# ToF.net
KiCad netlist of a schematic drawn in Altium Designer
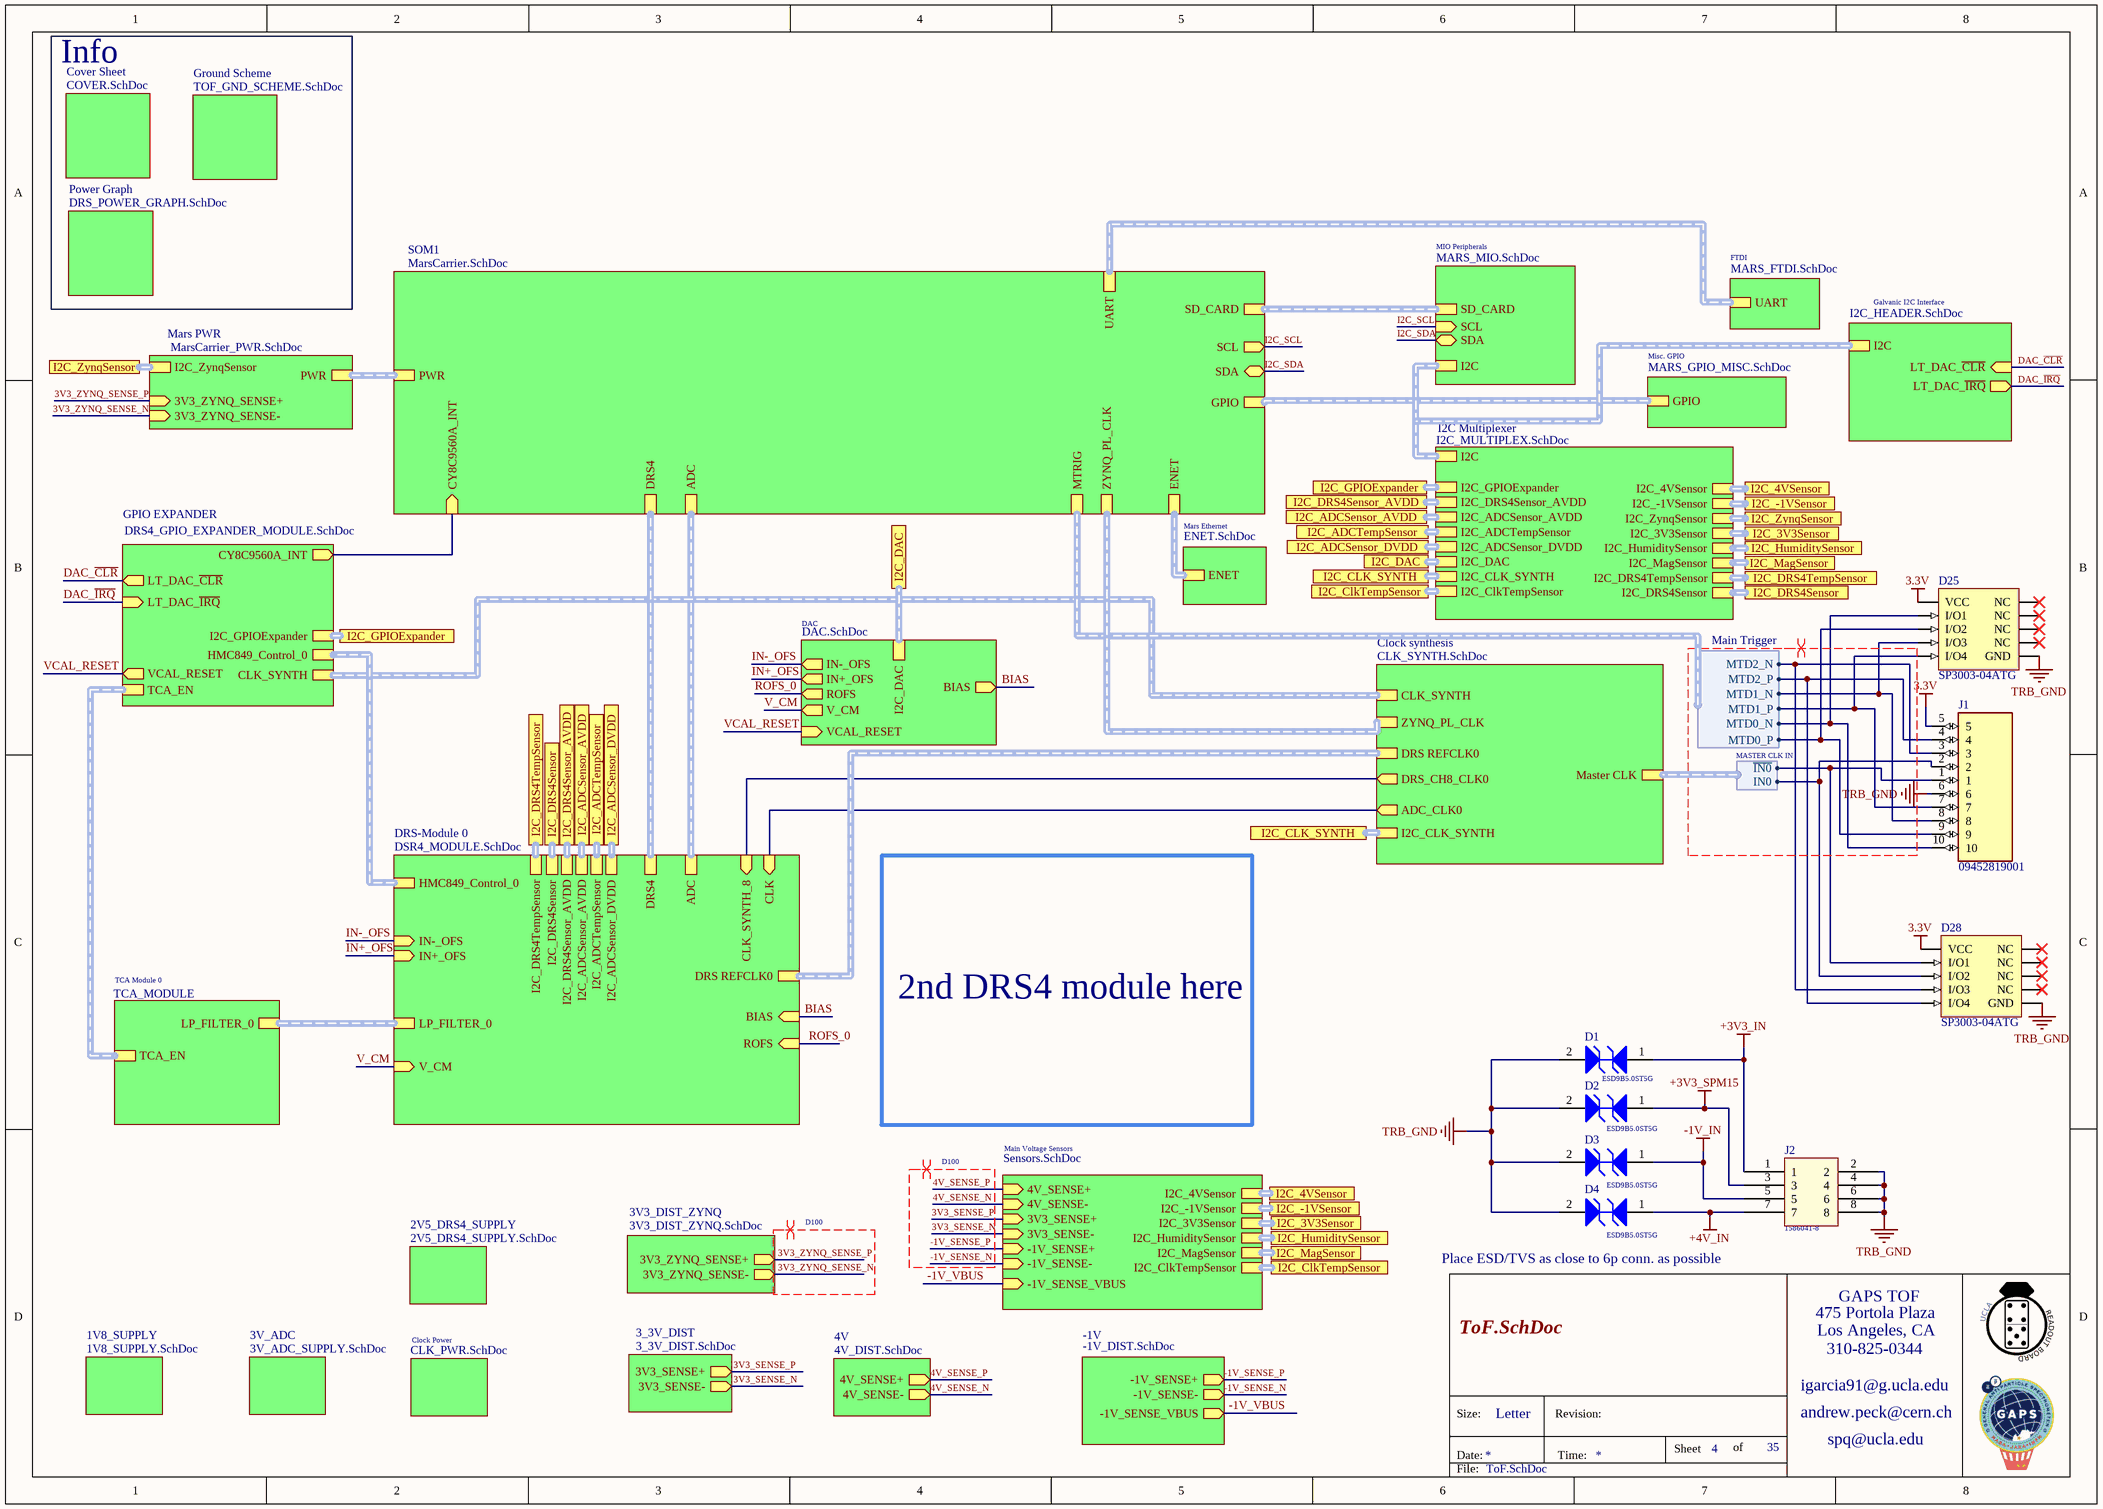
[diagram p0: ToF.SchDoc]

(export (version "E")
  (design (tool "Eeschema 10.0.6"))
  (components
    (comp (ref "D1")
      (value "ESD9B5.0ST5G")
      (footprint "ONSC-SOD-923-2-514AB-01_V")
      (fields (field (name "MANUFACTURER") "On Semiconductor"))
      (libsource (lib "On_Semiconductor_ESD9B5_0ST5G") (part "ESD9B5.0ST5G"))
    )
    (comp (ref "D2")
      (value "ESD9B5.0ST5G")
      (footprint "ONSC-SOD-923-2-514AB-01_V")
      (fields (field (name "MANUFACTURER") "On Semiconductor"))
      (libsource (lib "On_Semiconductor_ESD9B5_0ST5G") (part "ESD9B5.0ST5G"))
    )
    (comp (ref "D3")
      (value "ESD9B5.0ST5G")
      (footprint "ONSC-SOD-923-2-514AB-01_V")
      (fields (field (name "MANUFACTURER") "On Semiconductor"))
      (libsource (lib "On_Semiconductor_ESD9B5_0ST5G") (part "ESD9B5.0ST5G"))
    )
    (comp (ref "D4")
      (value "ESD9B5.0ST5G")
      (footprint "ONSC-SOD-923-2-514AB-01_V")
      (fields (field (name "MANUFACTURER") "On Semiconductor"))
      (libsource (lib "On_Semiconductor_ESD9B5_0ST5G") (part "ESD9B5.0ST5G"))
    )
    (comp (ref "D25")
      (value "Diode_SP3003-04ATG_LVDS_ESD")
      (footprint "Diode_SP3003-04ATG_LVDS_ESD")
      (description "ESD Suppressors / TVS Diodes 4 Ch 8kV 0.65pF SPA")
      (fields (field (name "SERIES") "SP3003-04ATG"))
      (libsource (lib "Diode_SP3003-04ATG_LVDS_ESD") (part "Diode_SP3003-04ATG_LVDS_ESD"))
    )
    (comp (ref "D28")
      (value "Diode_SP3003-04ATG_LVDS_ESD")
      (footprint "Diode_SP3003-04ATG_LVDS_ESD")
      (description "ESD Suppressors / TVS Diodes 4 Ch 8kV 0.65pF SPA")
      (fields (field (name "SERIES") "SP3003-04ATG"))
      (libsource (lib "Diode_SP3003-04ATG_LVDS_ESD") (part "Diode_SP3003-04ATG_LVDS_ESD"))
    )
    (comp (ref "J1")
      (value "09452819001")
      (footprint "09452812561")
      (description "Connector")
      (fields (field (name "MOUSER PART NUMBER") "617-09452819001"))
      (libsource (lib "Conn_Harting_09452819001") (part "09452819001"))
    )
    (comp (ref "J2")
      (value "Header_TE_Connectivity_1586041-8_8POS")
      (footprint "Header_TE_Connectivity_1586041-8_8POS")
      (description "Headers & Wire Housings RA HDR W/O PEGS 8P")
      (fields (field (name "SERIES") "1586041-8"))
      (libsource (lib "Header_TE_Connectivity_1586041-8_8POS") (part "Header_TE_Connectivity_1586041-8_8POS"))
    )
  )
  (nets
    (net (code "70") (name "+3V3_IN") (class "Default")
      (node (ref "D1") (pin "1") (pinfunction "A1_1") (pintype "passive"))
      (node (ref "J2") (pin "1") (pinfunction "1_1") (pintype "power_in"))
    )
    (net (code "71") (name "+3V3_SPM15") (class "Default")
      (node (ref "D2") (pin "1") (pinfunction "A1_1") (pintype "passive"))
      (node (ref "J2") (pin "3") (pinfunction "3_3") (pintype "power_in"))
    )
    (net (code "72") (name "+4V_IN") (class "Default")
      (node (ref "D4") (pin "1") (pinfunction "A1_1") (pintype "passive"))
      (node (ref "J2") (pin "7") (pinfunction "7_7") (pintype "power_in"))
    )
    (net (code "73") (name "-1V_IN") (class "Default")
      (node (ref "D3") (pin "1") (pinfunction "A1_1") (pintype "passive"))
      (node (ref "J2") (pin "5") (pinfunction "5_5") (pintype "power_in"))
    )
    (net (code "128") (name "3.3V") (class "Default")
      (node (ref "D25") (pin "3") (pinfunction "VCC_3") (pintype "passive"))
      (node (ref "D28") (pin "3") (pinfunction "VCC_3") (pintype "passive"))
      (node (ref "J1") (pin "5") (pinfunction "5_5") (pintype "bidirectional"))
    )
    (net (code "129") (name "Net-(D25-I{slash}O1)") (class "Default")
      (node (ref "D25") (pin "1") (pinfunction "I/O1_1") (pintype "input"))
      (node (ref "J1") (pin "10") (pinfunction "10_10") (pintype "bidirectional"))
    )
    (net (code "130") (name "Net-(D25-I{slash}O2)") (class "Default")
      (node (ref "D25") (pin "2") (pinfunction "I/O2_2") (pintype "input"))
      (node (ref "J1") (pin "9") (pinfunction "9_9") (pintype "bidirectional"))
    )
    (net (code "131") (name "Net-(D25-I{slash}O3)") (class "Default")
      (node (ref "D25") (pin "4") (pinfunction "I/O3_4") (pintype "input"))
      (node (ref "J1") (pin "8") (pinfunction "8_8") (pintype "bidirectional"))
    )
    (net (code "132") (name "Net-(D25-I{slash}O4)") (class "Default")
      (node (ref "D25") (pin "5") (pinfunction "I/O4_5") (pintype "input"))
      (node (ref "J1") (pin "7") (pinfunction "7_7") (pintype "bidirectional"))
    )
    (net (code "133") (name "Net-(D28-I{slash}O1)") (class "Default")
      (node (ref "D28") (pin "1") (pinfunction "I/O1_1") (pintype "input"))
      (node (ref "J1") (pin "1") (pinfunction "1_1") (pintype "bidirectional"))
    )
    (net (code "134") (name "Net-(D28-I{slash}O2)") (class "Default")
      (node (ref "D28") (pin "2") (pinfunction "I/O2_2") (pintype "input"))
      (node (ref "J1") (pin "2") (pinfunction "2_2") (pintype "bidirectional"))
    )
    (net (code "135") (name "Net-(D28-I{slash}O3)") (class "Default")
      (node (ref "D28") (pin "4") (pinfunction "I/O3_4") (pintype "input"))
      (node (ref "J1") (pin "3") (pinfunction "3_3") (pintype "bidirectional"))
    )
    (net (code "136") (name "Net-(D28-I{slash}O4)") (class "Default")
      (node (ref "D28") (pin "5") (pinfunction "I/O4_5") (pintype "input"))
      (node (ref "J1") (pin "4") (pinfunction "4_4") (pintype "bidirectional"))
    )
    (net (code "137") (name "TRB_GND") (class "Default")
      (node (ref "D1") (pin "2") (pinfunction "A2_2") (pintype "passive"))
      (node (ref "D2") (pin "2") (pinfunction "A2_2") (pintype "passive"))
      (node (ref "D25") (pin "8") (pinfunction "GND_8") (pintype "power_in"))
      (node (ref "D28") (pin "8") (pinfunction "GND_8") (pintype "power_in"))
      (node (ref "D3") (pin "2") (pinfunction "A2_2") (pintype "passive"))
      (node (ref "D4") (pin "2") (pinfunction "A2_2") (pintype "passive"))
      (node (ref "J1") (pin "6") (pinfunction "6_6") (pintype "bidirectional"))
      (node (ref "J2") (pin "2") (pinfunction "2_2") (pintype "passive"))
      (node (ref "J2") (pin "4") (pinfunction "4_4") (pintype "passive"))
      (node (ref "J2") (pin "6") (pinfunction "6_6") (pintype "passive"))
      (node (ref "J2") (pin "8") (pinfunction "8_8") (pintype "passive"))
    )
    (net (code "138") (name "unconnected-(D25-NC-Pad6)") (class "Default")
      (node (ref "D25") (pin "6") (pinfunction "NC_6") (pintype "tri_state+no_connect"))
    )
    (net (code "139") (name "unconnected-(D25-NC-Pad7)") (class "Default")
      (node (ref "D25") (pin "7") (pinfunction "NC_7") (pintype "tri_state+no_connect"))
    )
    (net (code "140") (name "unconnected-(D25-NC-Pad9)") (class "Default")
      (node (ref "D25") (pin "9") (pinfunction "NC_9") (pintype "tri_state+no_connect"))
    )
    (net (code "141") (name "unconnected-(D25-NC-Pad10)") (class "Default")
      (node (ref "D25") (pin "10") (pinfunction "NC_10") (pintype "tri_state+no_connect"))
    )
    (net (code "142") (name "unconnected-(D28-NC-Pad6)") (class "Default")
      (node (ref "D28") (pin "6") (pinfunction "NC_6") (pintype "tri_state+no_connect"))
    )
    (net (code "143") (name "unconnected-(D28-NC-Pad7)") (class "Default")
      (node (ref "D28") (pin "7") (pinfunction "NC_7") (pintype "tri_state+no_connect"))
    )
    (net (code "144") (name "unconnected-(D28-NC-Pad9)") (class "Default")
      (node (ref "D28") (pin "9") (pinfunction "NC_9") (pintype "tri_state+no_connect"))
    )
    (net (code "145") (name "unconnected-(D28-NC-Pad10)") (class "Default")
      (node (ref "D28") (pin "10") (pinfunction "NC_10") (pintype "tri_state+no_connect"))
    )
  )
)
